# IO.net
KiCad netlist of a schematic drawn in Altium Designer
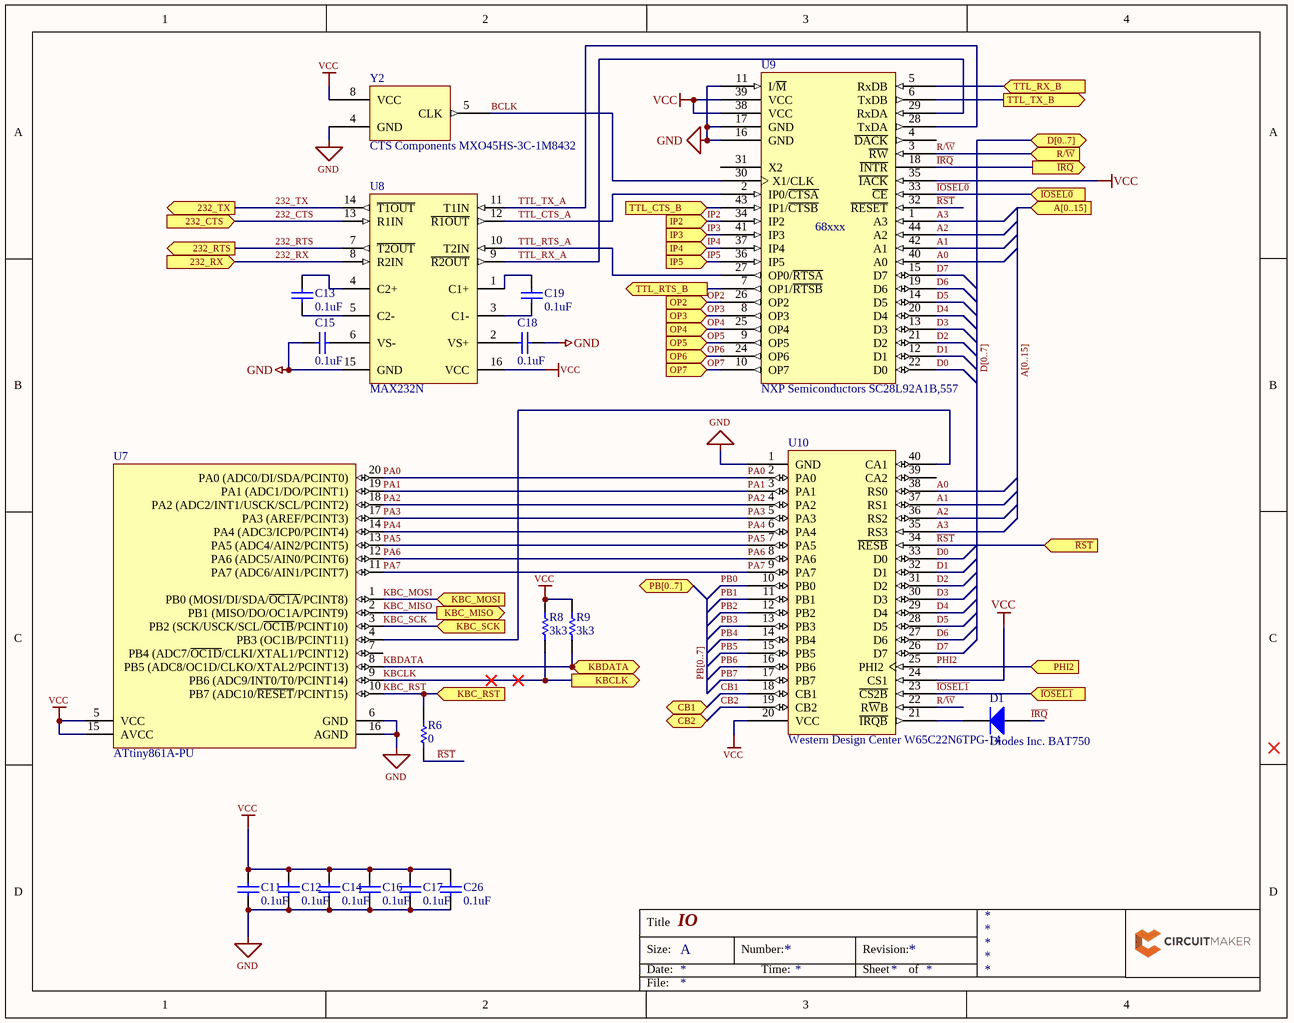
[diagram p0: IO.SchDoc]

(export (version "E")
  (design (tool "Eeschema 10.0.6"))
  (components
    (comp (ref "C11")
      (value "0.1uF")
      (footprint "CAPC1608X90X35NL15T15")
      (description "0603 0.1uF Capacitor")
      (libsource (lib "CommunityVault") (part "CAP-2"))
    )
    (comp (ref "C12")
      (value "0.1uF")
      (footprint "CAPC1608X90X35NL15T15")
      (description "0603 0.1uF Capacitor")
      (libsource (lib "CommunityVault") (part "CAP-2"))
    )
    (comp (ref "C13")
      (value "0.1uF")
      (footprint "CAPC1608X90X35NL15T15")
      (description "0603 0.1uF Capacitor")
      (libsource (lib "CommunityVault") (part "CAP-2"))
    )
    (comp (ref "C14")
      (value "0.1uF")
      (footprint "CAPC1608X90X35NL15T15")
      (description "0603 0.1uF Capacitor")
      (libsource (lib "CommunityVault") (part "CAP-2"))
    )
    (comp (ref "C15")
      (value "0.1uF")
      (footprint "CAPC1608X90X35NL15T15")
      (description "0603 0.1uF Capacitor")
      (libsource (lib "CommunityVault") (part "CAP-2"))
    )
    (comp (ref "C16")
      (value "0.1uF")
      (footprint "CAPC1608X90X35NL15T15")
      (description "0603 0.1uF Capacitor")
      (libsource (lib "CommunityVault") (part "CAP-2"))
    )
    (comp (ref "C17")
      (value "0.1uF")
      (footprint "CAPC1608X90X35NL15T15")
      (description "0603 0.1uF Capacitor")
      (libsource (lib "CommunityVault") (part "CAP-2"))
    )
    (comp (ref "C18")
      (value "0.1uF")
      (footprint "CAPC1608X90X35NL15T15")
      (description "0603 0.1uF Capacitor")
      (libsource (lib "CommunityVault") (part "CAP-2"))
    )
    (comp (ref "C19")
      (value "0.1uF")
      (footprint "CAPC1608X90X35NL15T15")
      (description "0603 0.1uF Capacitor")
      (libsource (lib "CommunityVault") (part "CAP-2"))
    )
    (comp (ref "C26")
      (value "0.1uF")
      (footprint "CAPC1608X90X35NL15T15")
      (description "0603 0.1uF Capacitor")
      (libsource (lib "CommunityVault") (part "CMP-15328962-11"))
    )
    (comp (ref "D1")
      (value "Diodes Inc. BAT750")
      (footprint "PCB-424japtr4l4h57iluqnj-1")
      (description "VR = 40V  IF = 750mA  VF < 490mV @ 750mA SOT23")
      (fields (field (name "MANUFACTURER PART NUMBER") "BAT750"))
      (libsource (lib "FavoritesLibrary") (part "SYM-bfb87653b293607f-1"))
    )
    (comp (ref "R6")
      (value "0")
      (footprint "RESC1608X55X30ML20T10")
      (description "Thick Film Resistors - SMD 1/10watt 3.3Kohms 1%")
      (libsource (lib "CommunityVault") (part "RES-2"))
    )
    (comp (ref "R8")
      (value "3k3")
      (footprint "RESC1608X55X30ML20T10")
      (description "Thick Film Resistors - SMD 1/10watt 3.3Kohms 1%")
      (libsource (lib "CommunityVault") (part "CMP-3658446-2"))
    )
    (comp (ref "R9")
      (value "3k3")
      (footprint "RESC1608X55X30ML20T10")
      (description "Thick Film Resistors - SMD 1/10watt 3.3Kohms 1%")
      (libsource (lib "CommunityVault") (part "RES-2"))
    )
    (comp (ref "U7")
      (value "ATtiny861A-PU")
      (footprint "20P3")
      (libsource (lib "CommunityVault") (part "MC-8B-ATT261A-IL20"))
    )
    (comp (ref "U8")
      (value "MAX232N")
      (footprint "TI-N16")
      (description "Dual EIA-232 Driver / Receiver, 0 to 70 degC, 16-Pin PDIP (N), Pb-Free (RoHS)")
      (libsource (lib "CommunityVault") (part "TI-MAX232-PDIP_N-16"))
    )
    (comp (ref "U9")
      (value "NXP Semiconductors SC28L92A1B,557")
      (footprint "PCB-gqi0ukwbi8o3vwizgqut-1")
      (fields (field (name "MANUFACTURER PART NUMBER") "SC28L92A1B,557"))
      (libsource (lib "CommunityVault") (part "CMP-1b55d2ce0277c492-1"))
    )
    (comp (ref "U10")
      (value "Western Design Center W65C22N6TPG-14")
      (footprint "PCB-fzv7zhlkwo7pvhyncebf-1")
      (description "W65C22N Versatile Interface Adapter (VIA)")
      (fields (field (name "MANUFACTURER PART NUMBER") "W65C22N6TPG-14"))
      (libsource (lib "CommunityVault") (part "SYM-efc5278ec54e3002-1"))
    )
    (comp (ref "Y2")
      (value "CTS Components MXO45HS-3C-1M8432")
      (footprint "PCB-9wf0uyermkn85h0e2qa4-1")
      (description "Oscillator XO 1.8432MHz ±50ppm 50pF (Stability) HCMOS/TTL 55% 5V 4-Pin Metal DIP Thru-Hole Tray")
      (fields (field (name "MANUFACTURER PART NUMBER") "MXO45HS-3C-1M8432"))
      (libsource (lib "CommunityVault") (part "SYM-6487ad4d37bebb40-1"))
    )
  )
  (nets
    (net (code "13") (name "/232_CTS") (class "Default")
      (node (ref "U8") (pin "13") (pinfunction "R1IN_13") (pintype "input"))
    )
    (net (code "14") (name "/232_RTS") (class "Default")
      (node (ref "U8") (pin "7") (pinfunction "~{T2OUT}_7") (pintype "output"))
    )
    (net (code "15") (name "/232_RX") (class "Default")
      (node (ref "U8") (pin "8") (pinfunction "R2IN_8") (pintype "input"))
    )
    (net (code "16") (name "/232_TX") (class "Default")
      (node (ref "U8") (pin "14") (pinfunction "~{T1OUT}_14") (pintype "output"))
    )
    (net (code "17") (name "/A0") (class "Default")
      (node (ref "U10") (pin "38") (pinfunction "RS0_38") (pintype "bidirectional"))
      (node (ref "U9") (pin "40") (pinfunction "A0_40") (pintype "input"))
    )
    (net (code "18") (name "/A1") (class "Default")
      (node (ref "U10") (pin "37") (pinfunction "RS1_37") (pintype "bidirectional"))
      (node (ref "U9") (pin "42") (pinfunction "A1_42") (pintype "input"))
    )
    (net (code "19") (name "/A2") (class "Default")
      (node (ref "U10") (pin "36") (pinfunction "RS2_36") (pintype "bidirectional"))
      (node (ref "U9") (pin "44") (pinfunction "A2_44") (pintype "input"))
    )
    (net (code "20") (name "/A3") (class "Default")
      (node (ref "U10") (pin "35") (pinfunction "RS3_35") (pintype "input"))
      (node (ref "U9") (pin "1") (pinfunction "A3_1") (pintype "input"))
    )
    (net (code "22") (name "/BCLK") (class "Default")
      (node (ref "U9") (pin "30") (pinfunction "X1/CLK_30") (pintype "passive"))
      (node (ref "Y2") (pin "5") (pinfunction "CLK_5") (pintype "output"))
    )
    (net (code "23") (name "/CB1") (class "Default")
      (node (ref "U10") (pin "18") (pinfunction "CB1_18") (pintype "bidirectional"))
    )
    (net (code "24") (name "/CB2") (class "Default")
      (node (ref "U10") (pin "19") (pinfunction "CB2_19") (pintype "bidirectional"))
    )
    (net (code "25") (name "/D0") (class "Default")
      (node (ref "U10") (pin "33") (pinfunction "D0_33") (pintype "bidirectional"))
      (node (ref "U9") (pin "22") (pinfunction "D0_22") (pintype "bidirectional"))
    )
    (net (code "26") (name "/D1") (class "Default")
      (node (ref "U10") (pin "32") (pinfunction "D1_32") (pintype "bidirectional"))
      (node (ref "U9") (pin "12") (pinfunction "D1_12") (pintype "bidirectional"))
    )
    (net (code "27") (name "/D2") (class "Default")
      (node (ref "U10") (pin "31") (pinfunction "D2_31") (pintype "bidirectional"))
      (node (ref "U9") (pin "21") (pinfunction "D2_21") (pintype "bidirectional"))
    )
    (net (code "28") (name "/D3") (class "Default")
      (node (ref "U10") (pin "30") (pinfunction "D3_30") (pintype "bidirectional"))
      (node (ref "U9") (pin "13") (pinfunction "D3_13") (pintype "bidirectional"))
    )
    (net (code "29") (name "/D4") (class "Default")
      (node (ref "U10") (pin "29") (pinfunction "D4_29") (pintype "bidirectional"))
      (node (ref "U9") (pin "20") (pinfunction "D4_20") (pintype "bidirectional"))
    )
    (net (code "30") (name "/D5") (class "Default")
      (node (ref "U10") (pin "28") (pinfunction "D5_28") (pintype "bidirectional"))
      (node (ref "U9") (pin "14") (pinfunction "D5_14") (pintype "bidirectional"))
    )
    (net (code "31") (name "/D6") (class "Default")
      (node (ref "U10") (pin "27") (pinfunction "D6_27") (pintype "bidirectional"))
      (node (ref "U9") (pin "19") (pinfunction "D6_19") (pintype "bidirectional"))
    )
    (net (code "32") (name "/D7") (class "Default")
      (node (ref "U10") (pin "26") (pinfunction "D7_26") (pintype "bidirectional"))
      (node (ref "U9") (pin "15") (pinfunction "D7_15") (pintype "bidirectional"))
    )
    (net (code "34") (name "/IP2") (class "Default")
      (node (ref "U9") (pin "34") (pinfunction "IP2_34") (pintype "input"))
    )
    (net (code "35") (name "/IP3") (class "Default")
      (node (ref "U9") (pin "41") (pinfunction "IP3_41") (pintype "input"))
    )
    (net (code "36") (name "/IP4") (class "Default")
      (node (ref "U9") (pin "37") (pinfunction "IP4_37") (pintype "input"))
    )
    (net (code "37") (name "/IP5") (class "Default")
      (node (ref "U9") (pin "36") (pinfunction "IP5_36") (pintype "input"))
    )
    (net (code "38") (name "/KBCLK") (class "Default")
      (node (ref "R8") (pin "1") (pinfunction "1_1") (pintype "passive"))
      (node (ref "U7") (pin "9") (pinfunction "PB6_(ADC9/INT0/T0/PCINT14)_9") (pintype "bidirectional"))
    )
    (net (code "39") (name "/KBC_MISO") (class "Default")
      (node (ref "U7") (pin "2") (pinfunction "PB1_(MISO/DO/OC1A/PCINT9)_2") (pintype "bidirectional"))
    )
    (net (code "40") (name "/KBC_MOSI") (class "Default")
      (node (ref "U7") (pin "1") (pinfunction "PB0_(MOSI/DI/SDA/~{OC1A}/PCINT8)_1") (pintype "bidirectional"))
    )
    (net (code "41") (name "/KBC_RST") (class "Default")
      (node (ref "R6") (pin "1") (pinfunction "1_1") (pintype "passive"))
      (node (ref "U7") (pin "10") (pinfunction "PB7_(ADC10/~{RESET}/PCINT15)_10") (pintype "bidirectional"))
    )
    (net (code "42") (name "/KBC_SCK") (class "Default")
      (node (ref "U7") (pin "3") (pinfunction "PB2_(SCK/USCK/SCL/~{OC1B}/PCINT10)_3") (pintype "bidirectional"))
    )
    (net (code "43") (name "/KBDATA") (class "Default")
      (node (ref "R9") (pin "1") (pinfunction "1_1") (pintype "passive"))
      (node (ref "U7") (pin "8") (pinfunction "PB5_(ADC8/OC1D/CLKO/XTAL2/PCINT13)_8") (pintype "bidirectional"))
    )
    (net (code "44") (name "/OP2") (class "Default")
      (node (ref "U9") (pin "26") (pinfunction "OP2_26") (pintype "output"))
    )
    (net (code "45") (name "/OP3") (class "Default")
      (node (ref "U9") (pin "8") (pinfunction "OP3_8") (pintype "output"))
    )
    (net (code "46") (name "/OP4") (class "Default")
      (node (ref "U9") (pin "25") (pinfunction "OP4_25") (pintype "output"))
    )
    (net (code "47") (name "/OP5") (class "Default")
      (node (ref "U9") (pin "9") (pinfunction "OP5_9") (pintype "output"))
    )
    (net (code "48") (name "/OP6") (class "Default")
      (node (ref "U9") (pin "24") (pinfunction "OP6_24") (pintype "output"))
    )
    (net (code "49") (name "/OP7") (class "Default")
      (node (ref "U9") (pin "10") (pinfunction "OP7_10") (pintype "output"))
    )
    (net (code "50") (name "/PA0") (class "Default")
      (node (ref "U10") (pin "2") (pinfunction "PA0_2") (pintype "bidirectional"))
      (node (ref "U7") (pin "20") (pinfunction "PA0_(ADC0/DI/SDA/PCINT0)_20") (pintype "bidirectional"))
    )
    (net (code "51") (name "/PA1") (class "Default")
      (node (ref "U10") (pin "3") (pinfunction "PA1_3") (pintype "bidirectional"))
      (node (ref "U7") (pin "19") (pinfunction "PA1_(ADC1/DO/PCINT1)_19") (pintype "bidirectional"))
    )
    (net (code "52") (name "/PA2") (class "Default")
      (node (ref "U10") (pin "4") (pinfunction "PA2_4") (pintype "bidirectional"))
      (node (ref "U7") (pin "18") (pinfunction "PA2_(ADC2/INT1/USCK/SCL/PCINT2)_18") (pintype "bidirectional"))
    )
    (net (code "53") (name "/PA3") (class "Default")
      (node (ref "U10") (pin "5") (pinfunction "PA3_5") (pintype "bidirectional"))
      (node (ref "U7") (pin "17") (pinfunction "PA3_(AREF/PCINT3)_17") (pintype "bidirectional"))
    )
    (net (code "54") (name "/PA4") (class "Default")
      (node (ref "U10") (pin "6") (pinfunction "PA4_6") (pintype "bidirectional"))
      (node (ref "U7") (pin "14") (pinfunction "PA4_(ADC3/ICP0/PCINT4)_14") (pintype "bidirectional"))
    )
    (net (code "55") (name "/PA5") (class "Default")
      (node (ref "U10") (pin "7") (pinfunction "PA5_7") (pintype "bidirectional"))
      (node (ref "U7") (pin "13") (pinfunction "PA5_(ADC4/AIN2/PCINT5)_13") (pintype "bidirectional"))
    )
    (net (code "56") (name "/PA6") (class "Default")
      (node (ref "U10") (pin "8") (pinfunction "PA6_8") (pintype "bidirectional"))
      (node (ref "U7") (pin "12") (pinfunction "PA6_(ADC5/AIN0/PCINT6)_12") (pintype "bidirectional"))
    )
    (net (code "57") (name "/PA7") (class "Default")
      (node (ref "U10") (pin "9") (pinfunction "PA7_9") (pintype "bidirectional"))
      (node (ref "U7") (pin "11") (pinfunction "PA7_(ADC6/AIN1/PCINT7)_11") (pintype "bidirectional"))
    )
    (net (code "58") (name "/PB0") (class "Default")
      (node (ref "U10") (pin "10") (pinfunction "PB0_10") (pintype "bidirectional"))
    )
    (net (code "59") (name "/PB1") (class "Default")
      (node (ref "U10") (pin "11") (pinfunction "PB1_11") (pintype "bidirectional"))
    )
    (net (code "60") (name "/PB2") (class "Default")
      (node (ref "U10") (pin "12") (pinfunction "PB2_12") (pintype "bidirectional"))
    )
    (net (code "61") (name "/PB3") (class "Default")
      (node (ref "U10") (pin "13") (pinfunction "PB3_13") (pintype "bidirectional"))
    )
    (net (code "62") (name "/PB4") (class "Default")
      (node (ref "U10") (pin "14") (pinfunction "PB4_14") (pintype "bidirectional"))
    )
    (net (code "63") (name "/PB5") (class "Default")
      (node (ref "U10") (pin "15") (pinfunction "PB5_15") (pintype "bidirectional"))
    )
    (net (code "64") (name "/PB6") (class "Default")
      (node (ref "U10") (pin "16") (pinfunction "PB6_16") (pintype "bidirectional"))
    )
    (net (code "65") (name "/PB7") (class "Default")
      (node (ref "U10") (pin "17") (pinfunction "PB7_17") (pintype "bidirectional"))
    )
    (net (code "67") (name "/PHI2") (class "Default")
      (node (ref "U10") (pin "25") (pinfunction "PHI2_25") (pintype "input"))
    )
    (net (code "68") (name "/R{slash}~{W}") (class "Default")
      (node (ref "U10") (pin "22") (pinfunction "R~{W}B_22") (pintype "input"))
      (node (ref "U9") (pin "3") (pinfunction "~{RW}_3") (pintype "input"))
    )
    (net (code "69") (name "/TTL_CTS_A") (class "Default")
      (node (ref "U8") (pin "12") (pinfunction "~{R1OUT}_12") (pintype "output"))
      (node (ref "U9") (pin "2") (pinfunction "IP0/~{CTSA}_2") (pintype "input"))
    )
    (net (code "70") (name "/TTL_CTS_B") (class "Default")
      (node (ref "U9") (pin "43") (pinfunction "IP1/~{CTSB}_43") (pintype "input"))
    )
    (net (code "71") (name "/TTL_RTS_A") (class "Default")
      (node (ref "U8") (pin "10") (pinfunction "T2IN_10") (pintype "input"))
      (node (ref "U9") (pin "27") (pinfunction "OP0/~{RTSA}_27") (pintype "output"))
    )
    (net (code "72") (name "/TTL_RTS_B") (class "Default")
      (node (ref "U9") (pin "7") (pinfunction "OP1/~{RTSB}_7") (pintype "output"))
    )
    (net (code "73") (name "/TTL_RX_A") (class "Default")
      (node (ref "U8") (pin "9") (pinfunction "~{R2OUT}_9") (pintype "output"))
      (node (ref "U9") (pin "29") (pinfunction "RxDA_29") (pintype "input"))
    )
    (net (code "74") (name "/TTL_RX_B") (class "Default")
      (node (ref "U9") (pin "5") (pinfunction "RxDB_5") (pintype "input"))
    )
    (net (code "75") (name "/TTL_TX_A") (class "Default")
      (node (ref "U8") (pin "11") (pinfunction "T1IN_11") (pintype "input"))
      (node (ref "U9") (pin "28") (pinfunction "TxDA_28") (pintype "output"))
    )
    (net (code "76") (name "/TTL_TX_B") (class "Default")
      (node (ref "U9") (pin "6") (pinfunction "TxDB_6") (pintype "output"))
    )
    (net (code "77") (name "/~{IOSEL0}") (class "Default")
      (node (ref "U9") (pin "33") (pinfunction "~{CE}_33") (pintype "input"))
    )
    (net (code "78") (name "/~{IOSEL1}") (class "Default")
      (node (ref "U10") (pin "23") (pinfunction "~{CS2B}_23") (pintype "input"))
    )
    (net (code "79") (name "/~{IRQ}") (class "Default")
      (node (ref "D1") (pin "1") (pinfunction "A_1") (pintype "passive"))
      (node (ref "U9") (pin "18") (pinfunction "~{INTR}_18") (pintype "open_collector"))
    )
    (net (code "80") (name "/~{RST}") (class "Default")
      (node (ref "R6") (pin "2") (pinfunction "2_2") (pintype "passive"))
      (node (ref "U10") (pin "34") (pinfunction "~{RESB}_34") (pintype "input"))
      (node (ref "U9") (pin "32") (pinfunction "~{RESET}_32") (pintype "input"))
    )
    (net (code "81") (name "GND") (class "Default")
      (node (ref "C11") (pin "1") (pinfunction "1_1") (pintype "passive"))
      (node (ref "C12") (pin "1") (pinfunction "1_1") (pintype "passive"))
      (node (ref "C14") (pin "1") (pinfunction "1_1") (pintype "passive"))
      (node (ref "C15") (pin "1") (pinfunction "1_1") (pintype "passive"))
      (node (ref "C16") (pin "1") (pinfunction "1_1") (pintype "passive"))
      (node (ref "C17") (pin "1") (pinfunction "1_1") (pintype "passive"))
      (node (ref "C18") (pin "2") (pinfunction "2_2") (pintype "passive"))
      (node (ref "C26") (pin "1") (pinfunction "1_1") (pintype "passive"))
      (node (ref "U10") (pin "1") (pinfunction "GND_1") (pintype "power_in"))
      (node (ref "U7") (pin "16") (pinfunction "AGND_16") (pintype "power_in"))
      (node (ref "U7") (pin "6") (pinfunction "GND_6") (pintype "power_in"))
      (node (ref "U8") (pin "15") (pinfunction "GND_15") (pintype "power_in"))
      (node (ref "U9") (pin "11") (pinfunction "I/~{M}_11") (pintype "input"))
      (node (ref "U9") (pin "16") (pinfunction "GND_16") (pintype "power_in"))
      (node (ref "U9") (pin "17") (pinfunction "GND_17") (pintype "power_in"))
      (node (ref "Y2") (pin "4") (pinfunction "GND_4") (pintype "passive"))
    )
    (net (code "82") (name "Net-(D1-K)") (class "Default")
      (node (ref "D1") (pin "3") (pinfunction "K_3") (pintype "passive"))
      (node (ref "U10") (pin "21") (pinfunction "~{IRQB}_21") (pintype "output"))
    )
    (net (code "83") (name "Net-(U8-C1+)") (class "Default")
      (node (ref "C19") (pin "2") (pinfunction "2_2") (pintype "passive"))
      (node (ref "U8") (pin "1") (pinfunction "C1+_1") (pintype "passive"))
    )
    (net (code "84") (name "Net-(U8-C1-)") (class "Default")
      (node (ref "C19") (pin "1") (pinfunction "1_1") (pintype "passive"))
      (node (ref "U8") (pin "3") (pinfunction "C1-_3") (pintype "passive"))
    )
    (net (code "85") (name "Net-(U8-C2+)") (class "Default")
      (node (ref "C13") (pin "2") (pinfunction "2_2") (pintype "passive"))
      (node (ref "U8") (pin "4") (pinfunction "C2+_4") (pintype "passive"))
    )
    (net (code "86") (name "Net-(U8-C2-)") (class "Default")
      (node (ref "C13") (pin "1") (pinfunction "1_1") (pintype "passive"))
      (node (ref "U8") (pin "5") (pinfunction "C2-_5") (pintype "passive"))
    )
    (net (code "87") (name "Net-(U8-VS+)") (class "Default")
      (node (ref "C18") (pin "1") (pinfunction "1_1") (pintype "passive"))
      (node (ref "U8") (pin "2") (pinfunction "VS+_2") (pintype "power_in"))
    )
    (net (code "88") (name "Net-(U8-VS-)") (class "Default")
      (node (ref "C15") (pin "2") (pinfunction "2_2") (pintype "passive"))
      (node (ref "U8") (pin "6") (pinfunction "VS-_6") (pintype "power_in"))
    )
    (net (code "89") (name "Net-(U10-CA1)") (class "Default")
      (node (ref "U10") (pin "40") (pinfunction "CA1_40") (pintype "bidirectional"))
      (node (ref "U7") (pin "4") (pinfunction "PB3_(OC1B/PCINT11)_4") (pintype "bidirectional"))
    )
    (net (code "90") (name "VCC") (class "Default")
      (node (ref "C11") (pin "2") (pinfunction "2_2") (pintype "passive"))
      (node (ref "C12") (pin "2") (pinfunction "2_2") (pintype "passive"))
      (node (ref "C14") (pin "2") (pinfunction "2_2") (pintype "passive"))
      (node (ref "C16") (pin "2") (pinfunction "2_2") (pintype "passive"))
      (node (ref "C17") (pin "2") (pinfunction "2_2") (pintype "passive"))
      (node (ref "C26") (pin "2") (pinfunction "2_2") (pintype "passive"))
      (node (ref "R8") (pin "2") (pinfunction "2_2") (pintype "passive"))
      (node (ref "R9") (pin "2") (pinfunction "2_2") (pintype "passive"))
      (node (ref "U10") (pin "20") (pinfunction "VCC_20") (pintype "power_in"))
      (node (ref "U10") (pin "24") (pinfunction "CS1_24") (pintype "input"))
      (node (ref "U7") (pin "15") (pinfunction "AVCC_15") (pintype "power_in"))
      (node (ref "U7") (pin "5") (pinfunction "VCC_5") (pintype "power_in"))
      (node (ref "U8") (pin "16") (pinfunction "VCC_16") (pintype "power_in"))
      (node (ref "U9") (pin "35") (pinfunction "~{IACK}_35") (pintype "input"))
      (node (ref "U9") (pin "38") (pinfunction "VCC_38") (pintype "power_in"))
      (node (ref "U9") (pin "39") (pinfunction "VCC_39") (pintype "power_in"))
      (node (ref "Y2") (pin "8") (pinfunction "VCC_8") (pintype "passive"))
    )
    (net (code "91") (name "unconnected-(U7-PB4_(ADC7{slash}~{OC1D}{slash}CLKI{slash}XTAL1{slash}PCINT12)-Pad7)") (class "Default")
      (node (ref "U7") (pin "7") (pinfunction "PB4_(ADC7/~{OC1D}/CLKI/XTAL1/PCINT12)_7") (pintype "bidirectional"))
    )
    (net (code "92") (name "unconnected-(U9-NC-Pad23)") (class "Default")
      (node (ref "U9") (pin "23") (pinfunction "NC_23") (pintype "passive"))
    )
    (net (code "93") (name "unconnected-(U9-X2-Pad31)") (class "Default")
      (node (ref "U9") (pin "31") (pinfunction "X2_31") (pintype "passive"))
    )
    (net (code "94") (name "unconnected-(U9-~{DACK}-Pad4)") (class "Default")
      (node (ref "U9") (pin "4") (pinfunction "~{DACK}_4") (pintype "output"))
    )
    (net (code "95") (name "unconnected-(U10-CA2-Pad39)") (class "Default")
      (node (ref "U10") (pin "39") (pinfunction "CA2_39") (pintype "bidirectional"))
    )
  )
)
